# F4_mini2.net
KiCad netlist of a schematic drawn in EAGLE
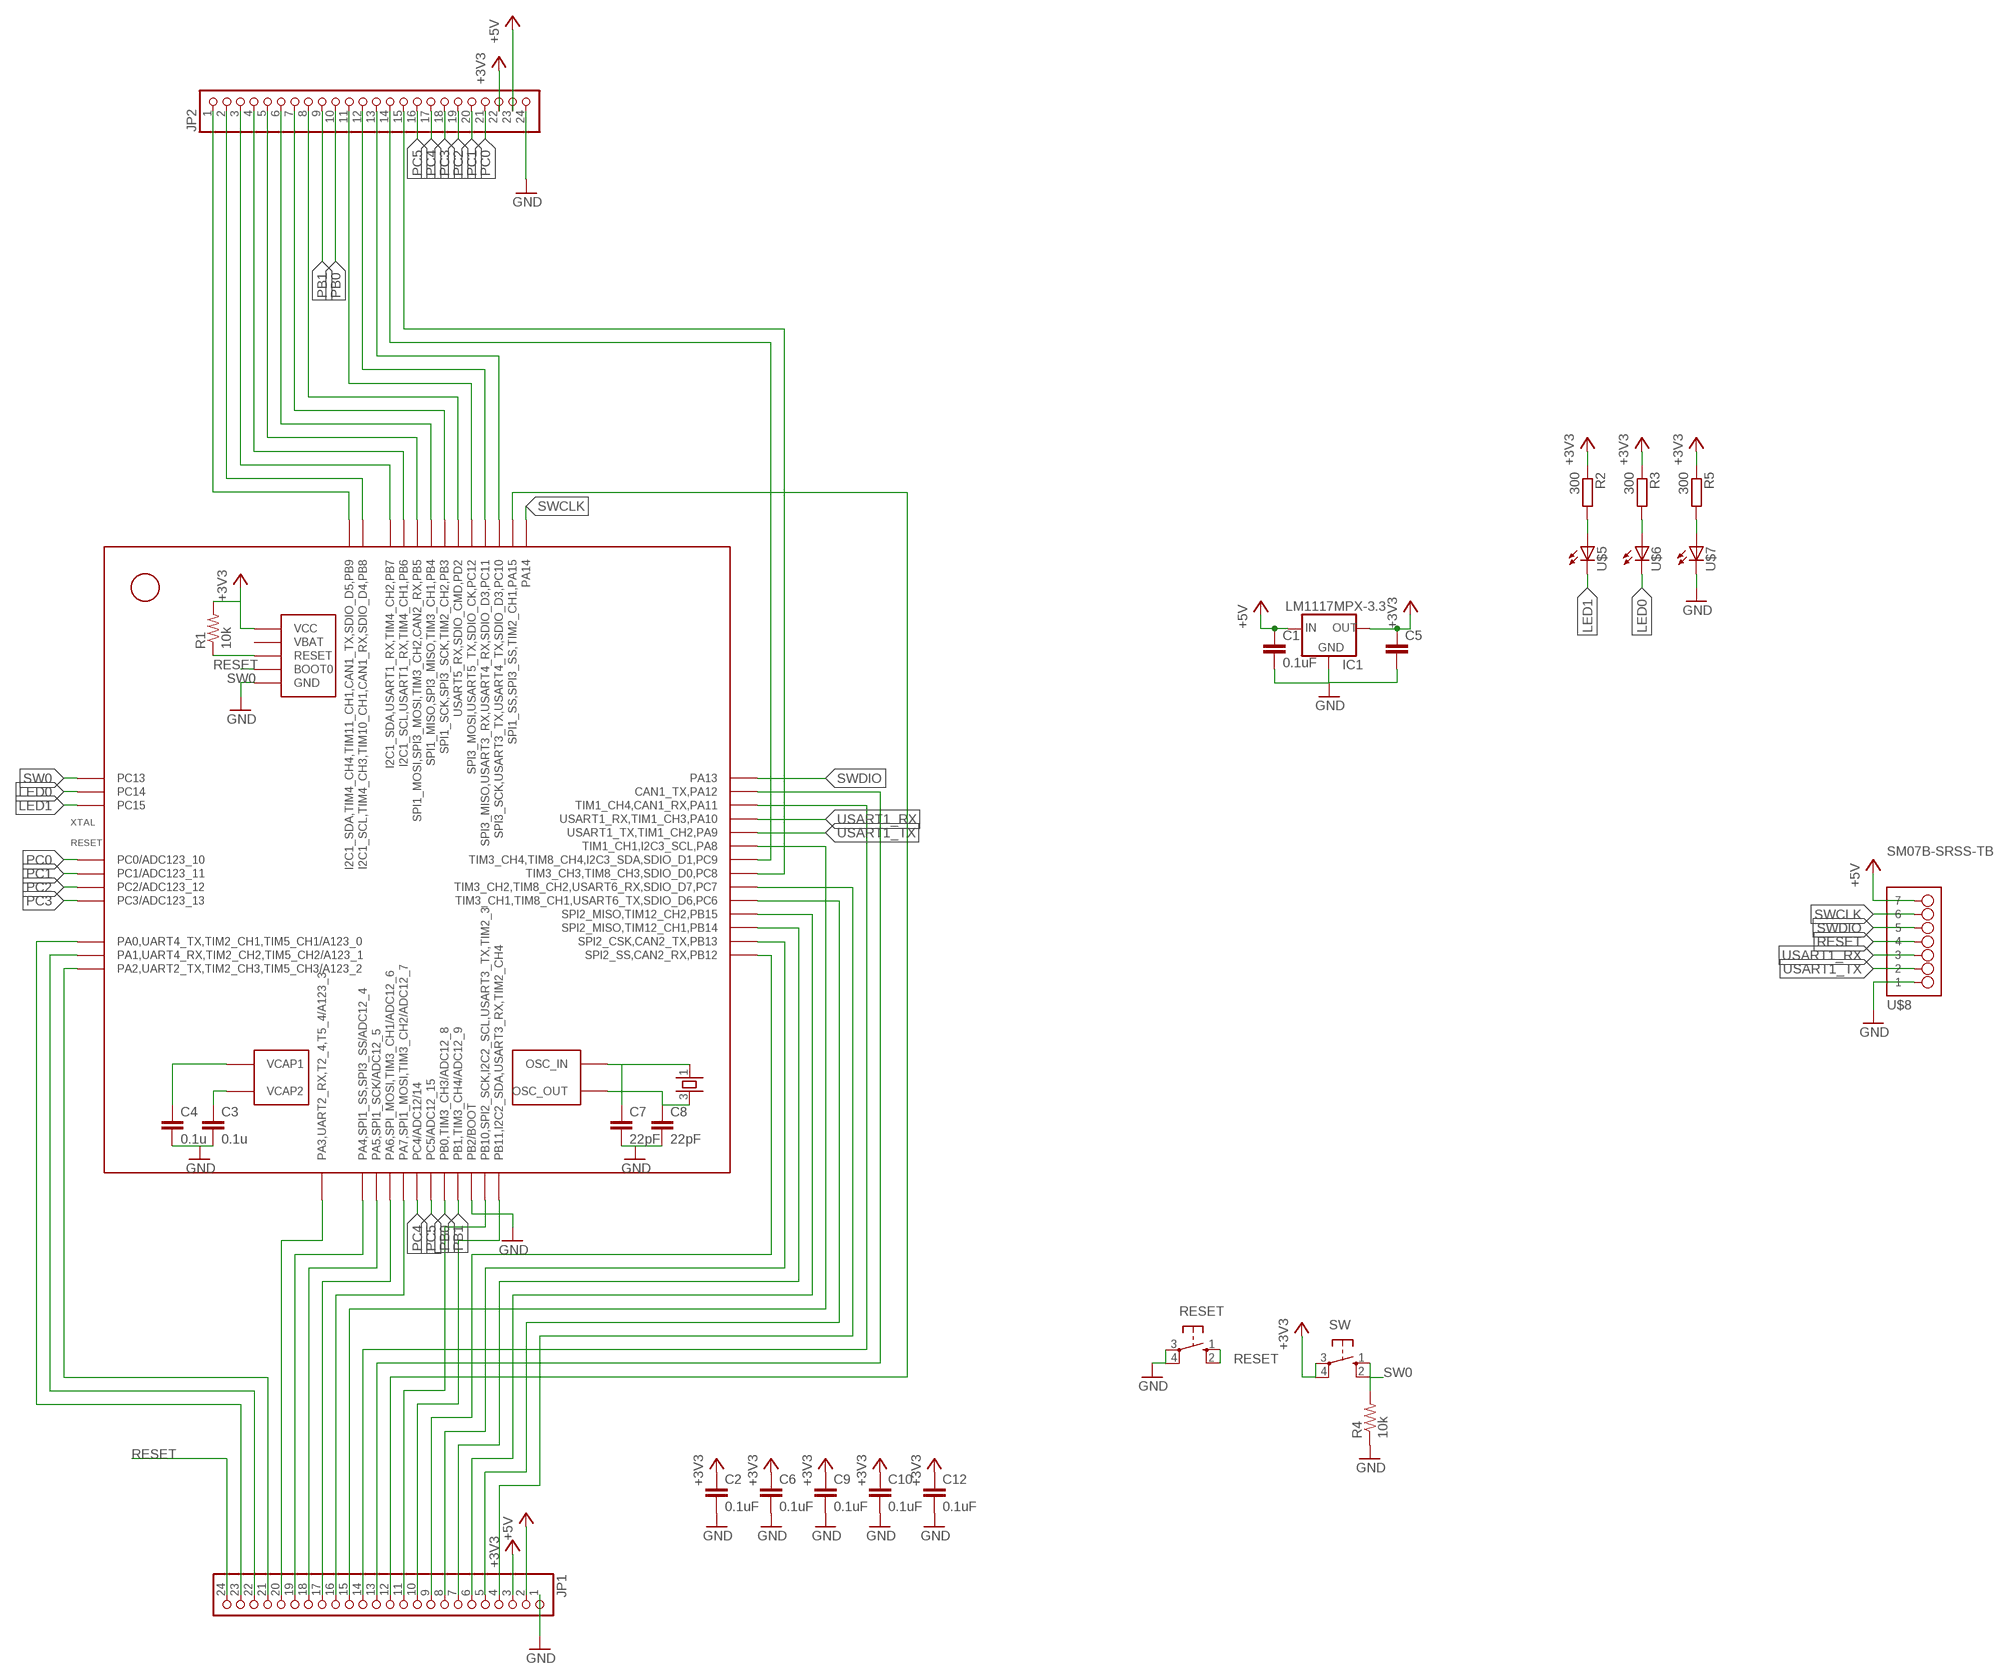
[diagram p0: schematic, sheet 1]

(export (version "E")
  (design (tool "Eeschema 10.0.6"))
  (components
    (comp (ref "C1")
      (value "0.1uF")
      (footprint "eagle-import:C0603K")
      (libsource (lib "eagle-import") (part "C-EUC0603K"))
    )
    (comp (ref "C2")
      (value "0.1uF")
      (footprint "eagle-import:C0603")
      (libsource (lib "eagle-import") (part "C-EUC0603"))
    )
    (comp (ref "C3")
      (value "0.1u")
      (footprint "eagle-import:C0603K")
      (libsource (lib "eagle-import") (part "C-EUC0603K"))
    )
    (comp (ref "C4")
      (value "0.1u")
      (footprint "eagle-import:C0603K")
      (libsource (lib "eagle-import") (part "C-EUC0603K"))
    )
    (comp (ref "C5")
      (value "C-EUC0603K")
      (footprint "eagle-import:C0603K")
      (libsource (lib "eagle-import") (part "C-EUC0603K"))
    )
    (comp (ref "C6")
      (value "0.1uF")
      (footprint "eagle-import:C0603")
      (libsource (lib "eagle-import") (part "C-EUC0603"))
    )
    (comp (ref "C7")
      (value "22pF")
      (footprint "eagle-import:C0603K")
      (libsource (lib "eagle-import") (part "C-EUC0603K"))
    )
    (comp (ref "C8")
      (value "22pF")
      (footprint "eagle-import:C0603K")
      (libsource (lib "eagle-import") (part "C-EUC0603K"))
    )
    (comp (ref "C9")
      (value "0.1uF")
      (footprint "eagle-import:C0603")
      (libsource (lib "eagle-import") (part "C-EUC0603"))
    )
    (comp (ref "C10")
      (value "0.1uF")
      (footprint "eagle-import:C0603")
      (libsource (lib "eagle-import") (part "C-EUC0603"))
    )
    (comp (ref "C12")
      (value "0.1uF")
      (footprint "eagle-import:C0603")
      (libsource (lib "eagle-import") (part "C-EUC0603"))
    )
    (comp (ref "IC1")
      (value "LM1117MPX-3.3")
      (footprint "eagle-import:SOT223")
      (libsource (lib "eagle-import") (part "LM1117"))
    )
    (comp (ref "JP1")
      (value "PINHD-1X24")
      (footprint "eagle-import:1X24")
      (libsource (lib "eagle-import") (part "PINHD-1X24"))
    )
    (comp (ref "JP2")
      (value "PINHD-1X24")
      (footprint "eagle-import:1X24")
      (libsource (lib "eagle-import") (part "PINHD-1X24"))
    )
    (comp (ref "R1")
      (value "10k")
      (footprint "eagle-import:R0603")
      (libsource (lib "eagle-import") (part "R-US_R0603"))
    )
    (comp (ref "R2")
      (value "300")
      (footprint "eagle-import:R0603")
      (libsource (lib "eagle-import") (part "R-EU_R0603"))
    )
    (comp (ref "R3")
      (value "300")
      (footprint "eagle-import:R0603")
      (libsource (lib "eagle-import") (part "R-EU_R0603"))
    )
    (comp (ref "R4")
      (value "10k")
      (footprint "eagle-import:R0603")
      (libsource (lib "eagle-import") (part "R-US_R0603"))
    )
    (comp (ref "R5")
      (value "300")
      (footprint "eagle-import:R0603")
      (libsource (lib "eagle-import") (part "R-EU_R0603"))
    )
    (comp (ref "RESET")
      (value "10-XX")
      (footprint "eagle-import:B3F-10XX")
      (fields (field (name "MPN") "B3F-1000"))
      (libsource (lib "eagle-import") (part "10-XX"))
    )
    (comp (ref "SW")
      (value "10-XX")
      (footprint "eagle-import:B3F-10XX")
      (fields (field (name "MPN") "B3F-1000"))
      (libsource (lib "eagle-import") (part "10-XX"))
    )
    (comp (ref "U$1")
      (value "STM32F405_T")
      (footprint "eagle-import:LQFP64")
      (libsource (lib "eagle-import") (part "STM32F405_T"))
    )
    (comp (ref "U$4")
      (value "25MHz")
      (footprint "eagle-import:ASF")
      (libsource (lib "eagle-import") (part "ASF_T"))
    )
    (comp (ref "U$5")
      (value "0603")
      (footprint "eagle-import:0603")
      (libsource (lib "eagle-import") (part "0603"))
    )
    (comp (ref "U$6")
      (value "0603")
      (footprint "eagle-import:0603")
      (libsource (lib "eagle-import") (part "0603"))
    )
    (comp (ref "U$7")
      (value "0603")
      (footprint "eagle-import:0603")
      (libsource (lib "eagle-import") (part "0603"))
    )
    (comp (ref "U$8")
      (value "SM07B-SRSS-TB")
      (footprint "eagle-import:SM07B-SRSS-TB")
      (libsource (lib "eagle-import") (part "SM07B-SRSS-TB"))
    )
  )
  (nets
    (net (code "1") (name "+3V3") (class "Default")
      (node (ref "C10") (pin "1") (pinfunction "1_1") (pintype "passive"))
      (node (ref "C12") (pin "1") (pinfunction "1_1") (pintype "passive"))
      (node (ref "C2") (pin "1") (pinfunction "1_1") (pintype "passive"))
      (node (ref "C5") (pin "1") (pinfunction "1_1") (pintype "passive"))
      (node (ref "C6") (pin "1") (pinfunction "1_1") (pintype "passive"))
      (node (ref "C9") (pin "1") (pinfunction "1_1") (pintype "passive"))
      (node (ref "IC1") (pin "2") (pinfunction "OUT1_2") (pintype "passive"))
      (node (ref "IC1") (pin "4") (pinfunction "OUT_4") (pintype "passive"))
      (node (ref "JP1") (pin "3") (pinfunction "3_3") (pintype "passive"))
      (node (ref "JP2") (pin "22") (pinfunction "22_22") (pintype "passive"))
      (node (ref "R1") (pin "2") (pinfunction "2_2") (pintype "passive"))
      (node (ref "R2") (pin "1") (pinfunction "1_1") (pintype "passive"))
      (node (ref "R3") (pin "1") (pinfunction "1_1") (pintype "passive"))
      (node (ref "R5") (pin "1") (pinfunction "1_1") (pintype "passive"))
      (node (ref "SW") (pin "3") (pinfunction "P_3") (pintype "passive"))
      (node (ref "SW") (pin "4") (pinfunction "P1_4") (pintype "passive"))
      (node (ref "U$1") (pin "13") (pinfunction "VCC_13") (pintype "bidirectional"))
      (node (ref "U$1") (pin "19") (pinfunction "VCC_19") (pintype "bidirectional"))
      (node (ref "U$1") (pin "32") (pinfunction "VCC_32") (pintype "bidirectional"))
      (node (ref "U$1") (pin "48") (pinfunction "VCC_48") (pintype "bidirectional"))
      (node (ref "U$1") (pin "64") (pinfunction "VCC_64") (pintype "bidirectional"))
    )
    (net (code "2") (name "+5V") (class "Default")
      (node (ref "C1") (pin "1") (pinfunction "1_1") (pintype "passive"))
      (node (ref "IC1") (pin "3") (pinfunction "IN_3") (pintype "input"))
      (node (ref "JP1") (pin "2") (pinfunction "2_2") (pintype "passive"))
      (node (ref "JP2") (pin "23") (pinfunction "23_23") (pintype "passive"))
      (node (ref "U$8") (pin "P$7") (pinfunction "7_P$7") (pintype "bidirectional"))
    )
    (net (code "3") (name "GND") (class "Default")
      (node (ref "C1") (pin "2") (pinfunction "2_2") (pintype "passive"))
      (node (ref "C10") (pin "2") (pinfunction "2_2") (pintype "passive"))
      (node (ref "C12") (pin "2") (pinfunction "2_2") (pintype "passive"))
      (node (ref "C2") (pin "2") (pinfunction "2_2") (pintype "passive"))
      (node (ref "C3") (pin "2") (pinfunction "2_2") (pintype "passive"))
      (node (ref "C4") (pin "2") (pinfunction "2_2") (pintype "passive"))
      (node (ref "C5") (pin "2") (pinfunction "2_2") (pintype "passive"))
      (node (ref "C6") (pin "2") (pinfunction "2_2") (pintype "passive"))
      (node (ref "C7") (pin "2") (pinfunction "2_2") (pintype "passive"))
      (node (ref "C8") (pin "2") (pinfunction "2_2") (pintype "passive"))
      (node (ref "C9") (pin "2") (pinfunction "2_2") (pintype "passive"))
      (node (ref "IC1") (pin "1") (pinfunction "GND_1") (pintype "input"))
      (node (ref "JP1") (pin "1") (pinfunction "1_1") (pintype "passive"))
      (node (ref "JP2") (pin "24") (pinfunction "24_24") (pintype "passive"))
      (node (ref "R4") (pin "1") (pinfunction "1_1") (pintype "passive"))
      (node (ref "RESET") (pin "3") (pinfunction "P_3") (pintype "passive"))
      (node (ref "RESET") (pin "4") (pinfunction "P1_4") (pintype "passive"))
      (node (ref "U$1") (pin "12") (pinfunction "GND_12") (pintype "bidirectional"))
      (node (ref "U$1") (pin "18") (pinfunction "GND_18") (pintype "bidirectional"))
      (node (ref "U$1") (pin "28") (pinfunction "PB2/BOOT_28") (pintype "bidirectional"))
      (node (ref "U$1") (pin "63") (pinfunction "GND_63") (pintype "bidirectional"))
      (node (ref "U$7") (pin "C") (pinfunction "C_C") (pintype "passive"))
      (node (ref "U$8") (pin "P$1") (pinfunction "1_P$1") (pintype "bidirectional"))
    )
    (net (code "4") (name "LED0") (class "Default")
      (node (ref "U$1") (pin "3") (pinfunction "PC14_3") (pintype "bidirectional"))
      (node (ref "U$6") (pin "C") (pinfunction "C_C") (pintype "passive"))
    )
    (net (code "5") (name "LED1") (class "Default")
      (node (ref "U$1") (pin "4") (pinfunction "PC15_4") (pintype "bidirectional"))
      (node (ref "U$5") (pin "C") (pinfunction "C_C") (pintype "passive"))
    )
    (net (code "6") (name "Net-(R2-Pad2)") (class "Default")
      (node (ref "R2") (pin "2") (pinfunction "2_2") (pintype "passive"))
      (node (ref "U$5") (pin "A") (pinfunction "A_A") (pintype "passive"))
    )
    (net (code "7") (name "Net-(R3-Pad2)") (class "Default")
      (node (ref "R3") (pin "2") (pinfunction "2_2") (pintype "passive"))
      (node (ref "U$6") (pin "A") (pinfunction "A_A") (pintype "passive"))
    )
    (net (code "8") (name "Net-(R5-Pad2)") (class "Default")
      (node (ref "R5") (pin "2") (pinfunction "2_2") (pintype "passive"))
      (node (ref "U$7") (pin "A") (pinfunction "A_A") (pintype "passive"))
    )
    (net (code "9") (name "Net-(U$1-CAN1_TX,PA12)") (class "Default")
      (node (ref "JP1") (pin "13") (pinfunction "13_13") (pintype "passive"))
      (node (ref "U$1") (pin "45") (pinfunction "CAN1_TX,PA12_45") (pintype "bidirectional"))
    )
    (net (code "10") (name "Net-(U$1-I2C1_SCL,TIM4_CH3,TIM10_CH1,CAN1_RX,SDIO_D4,PB8)") (class "Default")
      (node (ref "JP2") (pin "2") (pinfunction "2_2") (pintype "passive"))
      (node (ref "U$1") (pin "61") (pinfunction "I2C1_SCL,TIM4_CH3,TIM10_CH1,CAN1_RX,SDIO_D4,PB8_61") (pintype "bidirectional"))
    )
    (net (code "11") (name "Net-(U$1-I2C1_SCL,USART1_RX,TIM4_CH1,PB6)") (class "Default")
      (node (ref "JP2") (pin "4") (pinfunction "4_4") (pintype "passive"))
      (node (ref "U$1") (pin "58") (pinfunction "I2C1_SCL,USART1_RX,TIM4_CH1,PB6_58") (pintype "bidirectional"))
    )
    (net (code "12") (name "Net-(U$1-I2C1_SDA,TIM4_CH4,TIM11_CH1,CAN1_TX,SDIO_D5,PB9)") (class "Default")
      (node (ref "JP2") (pin "1") (pinfunction "1_1") (pintype "passive"))
      (node (ref "U$1") (pin "62") (pinfunction "I2C1_SDA,TIM4_CH4,TIM11_CH1,CAN1_TX,SDIO_D5,PB9_62") (pintype "bidirectional"))
    )
    (net (code "13") (name "Net-(U$1-I2C1_SDA,USART1_RX,TIM4_CH2,PB7)") (class "Default")
      (node (ref "JP2") (pin "3") (pinfunction "3_3") (pintype "passive"))
      (node (ref "U$1") (pin "59") (pinfunction "I2C1_SDA,USART1_RX,TIM4_CH2,PB7_59") (pintype "bidirectional"))
    )
    (net (code "14") (name "Net-(U$1-OSC_IN)") (class "Default")
      (node (ref "C7") (pin "1") (pinfunction "1_1") (pintype "passive"))
      (node (ref "U$1") (pin "5") (pinfunction "OSC_IN_5") (pintype "bidirectional"))
      (node (ref "U$4") (pin "1") (pinfunction "P$1_1") (pintype "bidirectional"))
    )
    (net (code "15") (name "Net-(U$1-OSC_OUT)") (class "Default")
      (node (ref "C8") (pin "1") (pinfunction "1_1") (pintype "passive"))
      (node (ref "U$1") (pin "6") (pinfunction "OSC_OUT_6") (pintype "bidirectional"))
      (node (ref "U$4") (pin "3") (pinfunction "P$2_3") (pintype "bidirectional"))
    )
    (net (code "16") (name "Net-(U$1-PA0,UART4_TX,TIM2_CH1,TIM5_CH1{slash}A123_0)") (class "Default")
      (node (ref "JP1") (pin "23") (pinfunction "23_23") (pintype "passive"))
      (node (ref "U$1") (pin "14") (pinfunction "PA0,UART4_TX,TIM2_CH1,TIM5_CH1/A123_0_14") (pintype "bidirectional"))
    )
    (net (code "17") (name "Net-(U$1-PA1,UART4_RX,TIM2_CH2,TIM5_CH2{slash}A123_1)") (class "Default")
      (node (ref "JP1") (pin "22") (pinfunction "22_22") (pintype "passive"))
      (node (ref "U$1") (pin "15") (pinfunction "PA1,UART4_RX,TIM2_CH2,TIM5_CH2/A123_1_15") (pintype "bidirectional"))
    )
    (net (code "18") (name "Net-(U$1-PA2,UART2_TX,TIM2_CH3,TIM5_CH3{slash}A123_2)") (class "Default")
      (node (ref "JP1") (pin "21") (pinfunction "21_21") (pintype "passive"))
      (node (ref "U$1") (pin "16") (pinfunction "PA2,UART2_TX,TIM2_CH3,TIM5_CH3/A123_2_16") (pintype "bidirectional"))
    )
    (net (code "19") (name "Net-(U$1-PA3,UART2_RX,T2_4,T5_4{slash}A123_3)") (class "Default")
      (node (ref "JP1") (pin "20") (pinfunction "20_20") (pintype "passive"))
      (node (ref "U$1") (pin "17") (pinfunction "PA3,UART2_RX,T2_4,T5_4/A123_3_17") (pintype "bidirectional"))
    )
    (net (code "20") (name "Net-(U$1-PA4,SPI1_SS,SPI3_SS{slash}ADC12_4)") (class "Default")
      (node (ref "JP1") (pin "19") (pinfunction "19_19") (pintype "passive"))
      (node (ref "U$1") (pin "20") (pinfunction "PA4,SPI1_SS,SPI3_SS/ADC12_4_20") (pintype "bidirectional"))
    )
    (net (code "21") (name "Net-(U$1-PA5,SPI1_SCK{slash}ADC12_5)") (class "Default")
      (node (ref "JP1") (pin "18") (pinfunction "18_18") (pintype "passive"))
      (node (ref "U$1") (pin "21") (pinfunction "PA5,SPI1_SCK/ADC12_5_21") (pintype "bidirectional"))
    )
    (net (code "22") (name "Net-(U$1-PA6,SPI_MOSI,TIM3_CH1{slash}ADC12_6)") (class "Default")
      (node (ref "JP1") (pin "17") (pinfunction "17_17") (pintype "passive"))
      (node (ref "U$1") (pin "22") (pinfunction "PA6,SPI_MOSI,TIM3_CH1/ADC12_6_22") (pintype "bidirectional"))
    )
    (net (code "23") (name "Net-(U$1-PA7,SPI1_MOSI,TIM3_CH2{slash}ADC12_7)") (class "Default")
      (node (ref "JP1") (pin "16") (pinfunction "16_16") (pintype "passive"))
      (node (ref "U$1") (pin "23") (pinfunction "PA7,SPI1_MOSI,TIM3_CH2/ADC12_7_23") (pintype "bidirectional"))
    )
    (net (code "24") (name "Net-(U$1-PB10,SPI2_SCK,I2C2_SCL,USART3_TX,TIM2_3)") (class "Default")
      (node (ref "JP1") (pin "11") (pinfunction "11_11") (pintype "passive"))
      (node (ref "U$1") (pin "29") (pinfunction "PB10,SPI2_SCK,I2C2_SCL,USART3_TX,TIM2_3_29") (pintype "bidirectional"))
    )
    (net (code "25") (name "Net-(U$1-PB11,I2C2_SDA,USART3_RX,TIM2_CH4)") (class "Default")
      (node (ref "JP1") (pin "10") (pinfunction "10_10") (pintype "passive"))
      (node (ref "U$1") (pin "30") (pinfunction "PB11,I2C2_SDA,USART3_RX,TIM2_CH4_30") (pintype "bidirectional"))
    )
    (net (code "26") (name "Net-(U$1-SPI1_MISO,SPI3_MISO,TIM3_CH1,PB4)") (class "Default")
      (node (ref "JP2") (pin "6") (pinfunction "6_6") (pintype "passive"))
      (node (ref "U$1") (pin "56") (pinfunction "SPI1_MISO,SPI3_MISO,TIM3_CH1,PB4_56") (pintype "bidirectional"))
    )
    (net (code "27") (name "Net-(U$1-SPI1_MOSI,SPI3_MOSI,TIM3_CH2,CAN2_RX,PB5)") (class "Default")
      (node (ref "JP2") (pin "5") (pinfunction "5_5") (pintype "passive"))
      (node (ref "U$1") (pin "57") (pinfunction "SPI1_MOSI,SPI3_MOSI,TIM3_CH2,CAN2_RX,PB5_57") (pintype "bidirectional"))
    )
    (net (code "28") (name "Net-(U$1-SPI1_SCK,SPI3_SCK,TIM2_CH2,PB3)") (class "Default")
      (node (ref "JP2") (pin "7") (pinfunction "7_7") (pintype "passive"))
      (node (ref "U$1") (pin "55") (pinfunction "SPI1_SCK,SPI3_SCK,TIM2_CH2,PB3_55") (pintype "bidirectional"))
    )
    (net (code "29") (name "Net-(U$1-SPI1_SS,SPI3_SS,TIM2_CH1,PA15)") (class "Default")
      (node (ref "JP1") (pin "12") (pinfunction "12_12") (pintype "passive"))
      (node (ref "U$1") (pin "50") (pinfunction "SPI1_SS,SPI3_SS,TIM2_CH1,PA15_50") (pintype "bidirectional"))
    )
    (net (code "30") (name "Net-(U$1-SPI2_CSK,CAN2_TX,PB13)") (class "Default")
      (node (ref "JP1") (pin "8") (pinfunction "8_8") (pintype "passive"))
      (node (ref "U$1") (pin "34") (pinfunction "SPI2_CSK,CAN2_TX,PB13_34") (pintype "bidirectional"))
    )
    (net (code "31") (name "Net-(U$1-SPI2_MISO,TIM12_CH1,PB14)") (class "Default")
      (node (ref "JP1") (pin "7") (pinfunction "7_7") (pintype "passive"))
      (node (ref "U$1") (pin "35") (pinfunction "SPI2_MISO,TIM12_CH1,PB14_35") (pintype "bidirectional"))
    )
    (net (code "32") (name "Net-(U$1-SPI2_MISO,TIM12_CH2,PB15)") (class "Default")
      (node (ref "JP1") (pin "6") (pinfunction "6_6") (pintype "passive"))
      (node (ref "U$1") (pin "36") (pinfunction "SPI2_MISO,TIM12_CH2,PB15_36") (pintype "bidirectional"))
    )
    (net (code "33") (name "Net-(U$1-SPI2_SS,CAN2_RX,PB12)") (class "Default")
      (node (ref "JP1") (pin "9") (pinfunction "9_9") (pintype "passive"))
      (node (ref "U$1") (pin "33") (pinfunction "SPI2_SS,CAN2_RX,PB12_33") (pintype "bidirectional"))
    )
    (net (code "34") (name "Net-(U$1-SPI3_MISO,USART3_RX,USART4_RX,SDIO_D3,PC11)") (class "Default")
      (node (ref "JP2") (pin "12") (pinfunction "12_12") (pintype "passive"))
      (node (ref "U$1") (pin "52") (pinfunction "SPI3_MISO,USART3_RX,USART4_RX,SDIO_D3,PC11_52") (pintype "bidirectional"))
    )
    (net (code "35") (name "Net-(U$1-SPI3_MOSI,USART5_TX,SDIO_CK,PC12)") (class "Default")
      (node (ref "JP2") (pin "11") (pinfunction "11_11") (pintype "passive"))
      (node (ref "U$1") (pin "53") (pinfunction "SPI3_MOSI,USART5_TX,SDIO_CK,PC12_53") (pintype "bidirectional"))
    )
    (net (code "36") (name "Net-(U$1-SPI3_SCK,USART3_TX,USART4_TX,SDIO_D3,PC10)") (class "Default")
      (node (ref "JP2") (pin "13") (pinfunction "13_13") (pintype "passive"))
      (node (ref "U$1") (pin "51") (pinfunction "SPI3_SCK,USART3_TX,USART4_TX,SDIO_D3,PC10_51") (pintype "bidirectional"))
    )
    (net (code "37") (name "Net-(U$1-TIM1_CH1,I2C3_SCL,PA8)") (class "Default")
      (node (ref "JP1") (pin "15") (pinfunction "15_15") (pintype "passive"))
      (node (ref "U$1") (pin "41") (pinfunction "TIM1_CH1,I2C3_SCL,PA8_41") (pintype "bidirectional"))
    )
    (net (code "38") (name "Net-(U$1-TIM1_CH4,CAN1_RX,PA11)") (class "Default")
      (node (ref "JP1") (pin "14") (pinfunction "14_14") (pintype "passive"))
      (node (ref "U$1") (pin "44") (pinfunction "TIM1_CH4,CAN1_RX,PA11_44") (pintype "bidirectional"))
    )
    (net (code "39") (name "Net-(U$1-TIM3_CH1,TIM8_CH1,USART6_TX,SDIO_D6,PC6)") (class "Default")
      (node (ref "JP1") (pin "5") (pinfunction "5_5") (pintype "passive"))
      (node (ref "U$1") (pin "37") (pinfunction "TIM3_CH1,TIM8_CH1,USART6_TX,SDIO_D6,PC6_37") (pintype "bidirectional"))
    )
    (net (code "40") (name "Net-(U$1-TIM3_CH2,TIM8_CH2,USART6_RX,SDIO_D7,PC7)") (class "Default")
      (node (ref "JP1") (pin "4") (pinfunction "4_4") (pintype "passive"))
      (node (ref "U$1") (pin "38") (pinfunction "TIM3_CH2,TIM8_CH2,USART6_RX,SDIO_D7,PC7_38") (pintype "bidirectional"))
    )
    (net (code "41") (name "Net-(U$1-TIM3_CH3,TIM8_CH3,SDIO_D0,PC8)") (class "Default")
      (node (ref "JP2") (pin "15") (pinfunction "15_15") (pintype "passive"))
      (node (ref "U$1") (pin "39") (pinfunction "TIM3_CH3,TIM8_CH3,SDIO_D0,PC8_39") (pintype "bidirectional"))
    )
    (net (code "42") (name "Net-(U$1-TIM3_CH4,TIM8_CH4,I2C3_SDA,SDIO_D1,PC9)") (class "Default")
      (node (ref "JP2") (pin "14") (pinfunction "14_14") (pintype "passive"))
      (node (ref "U$1") (pin "40") (pinfunction "TIM3_CH4,TIM8_CH4,I2C3_SDA,SDIO_D1,PC9_40") (pintype "bidirectional"))
    )
    (net (code "43") (name "Net-(U$1-USART5_RX,SDIO_CMD,PD2)") (class "Default")
      (node (ref "JP2") (pin "8") (pinfunction "8_8") (pintype "passive"))
      (node (ref "U$1") (pin "54") (pinfunction "USART5_RX,SDIO_CMD,PD2_54") (pintype "bidirectional"))
    )
    (net (code "44") (name "Net-(U$1-VCAP1)") (class "Default")
      (node (ref "C4") (pin "1") (pinfunction "1_1") (pintype "passive"))
      (node (ref "U$1") (pin "31") (pinfunction "VCAP1_31") (pintype "bidirectional"))
    )
    (net (code "45") (name "Net-(U$1-VCAP2)") (class "Default")
      (node (ref "C3") (pin "1") (pinfunction "1_1") (pintype "passive"))
      (node (ref "U$1") (pin "47") (pinfunction "VCAP2_47") (pintype "bidirectional"))
    )
    (net (code "46") (name "PB0") (class "Default")
      (node (ref "JP2") (pin "10") (pinfunction "10_10") (pintype "passive"))
      (node (ref "U$1") (pin "26") (pinfunction "PB0,TIM3_CH3/ADC12_8_26") (pintype "bidirectional"))
    )
    (net (code "47") (name "PB1") (class "Default")
      (node (ref "JP2") (pin "9") (pinfunction "9_9") (pintype "passive"))
      (node (ref "U$1") (pin "27") (pinfunction "PB1,TIM3_CH4/ADC12_9_27") (pintype "bidirectional"))
    )
    (net (code "48") (name "PC0") (class "Default")
      (node (ref "JP2") (pin "21") (pinfunction "21_21") (pintype "passive"))
      (node (ref "U$1") (pin "8") (pinfunction "PC0/ADC123_10_8") (pintype "bidirectional"))
    )
    (net (code "49") (name "PC1") (class "Default")
      (node (ref "JP2") (pin "20") (pinfunction "20_20") (pintype "passive"))
      (node (ref "U$1") (pin "9") (pinfunction "PC1/ADC123_11_9") (pintype "bidirectional"))
    )
    (net (code "50") (name "PC2") (class "Default")
      (node (ref "JP2") (pin "19") (pinfunction "19_19") (pintype "passive"))
      (node (ref "U$1") (pin "10") (pinfunction "PC2/ADC123_12_10") (pintype "bidirectional"))
    )
    (net (code "51") (name "PC3") (class "Default")
      (node (ref "JP2") (pin "18") (pinfunction "18_18") (pintype "passive"))
      (node (ref "U$1") (pin "11") (pinfunction "PC3/ADC123_13_11") (pintype "bidirectional"))
    )
    (net (code "52") (name "PC4") (class "Default")
      (node (ref "JP2") (pin "17") (pinfunction "17_17") (pintype "passive"))
      (node (ref "U$1") (pin "24") (pinfunction "PC4/ADC12/14_24") (pintype "bidirectional"))
    )
    (net (code "53") (name "PC5") (class "Default")
      (node (ref "JP2") (pin "16") (pinfunction "16_16") (pintype "passive"))
      (node (ref "U$1") (pin "25") (pinfunction "PC5/ADC12_15_25") (pintype "bidirectional"))
    )
    (net (code "54") (name "RESET") (class "Default")
      (node (ref "JP1") (pin "24") (pinfunction "24_24") (pintype "passive"))
      (node (ref "R1") (pin "1") (pinfunction "1_1") (pintype "passive"))
      (node (ref "RESET") (pin "1") (pinfunction "S_1") (pintype "passive"))
      (node (ref "RESET") (pin "2") (pinfunction "S1_2") (pintype "passive"))
      (node (ref "U$1") (pin "7") (pinfunction "RESET_7") (pintype "bidirectional"))
      (node (ref "U$8") (pin "P$4") (pinfunction "4_P$4") (pintype "bidirectional"))
    )
    (net (code "55") (name "SW0") (class "Default")
      (node (ref "R4") (pin "2") (pinfunction "2_2") (pintype "passive"))
      (node (ref "SW") (pin "1") (pinfunction "S_1") (pintype "passive"))
      (node (ref "SW") (pin "2") (pinfunction "S1_2") (pintype "passive"))
      (node (ref "U$1") (pin "2") (pinfunction "PC13_2") (pintype "bidirectional"))
      (node (ref "U$1") (pin "60") (pinfunction "BOOT0_60") (pintype "bidirectional"))
    )
    (net (code "56") (name "SWCLK") (class "Default")
      (node (ref "U$1") (pin "49") (pinfunction "PA14_49") (pintype "bidirectional"))
      (node (ref "U$8") (pin "P$6") (pinfunction "6_P$6") (pintype "bidirectional"))
    )
    (net (code "57") (name "SWDIO") (class "Default")
      (node (ref "U$1") (pin "46") (pinfunction "PA13_46") (pintype "bidirectional"))
      (node (ref "U$8") (pin "P$5") (pinfunction "5_P$5") (pintype "bidirectional"))
    )
    (net (code "58") (name "USART1_RX") (class "Default")
      (node (ref "U$1") (pin "43") (pinfunction "USART1_RX,TIM1_CH3,PA10_43") (pintype "bidirectional"))
      (node (ref "U$8") (pin "P$3") (pinfunction "3_P$3") (pintype "bidirectional"))
    )
    (net (code "59") (name "USART1_TX") (class "Default")
      (node (ref "U$1") (pin "42") (pinfunction "USART1_TX,TIM1_CH2,PA9_42") (pintype "bidirectional"))
      (node (ref "U$8") (pin "P$2") (pinfunction "2_P$2") (pintype "bidirectional"))
    )
    (net (code "60") (name "unconnected-(U$1-VBAT-Pad1)") (class "Default")
      (node (ref "U$1") (pin "1") (pinfunction "VBAT_1") (pintype "bidirectional"))
    )
  )
)
